# main.net
KiCad netlist of a schematic drawn in Altium Designer
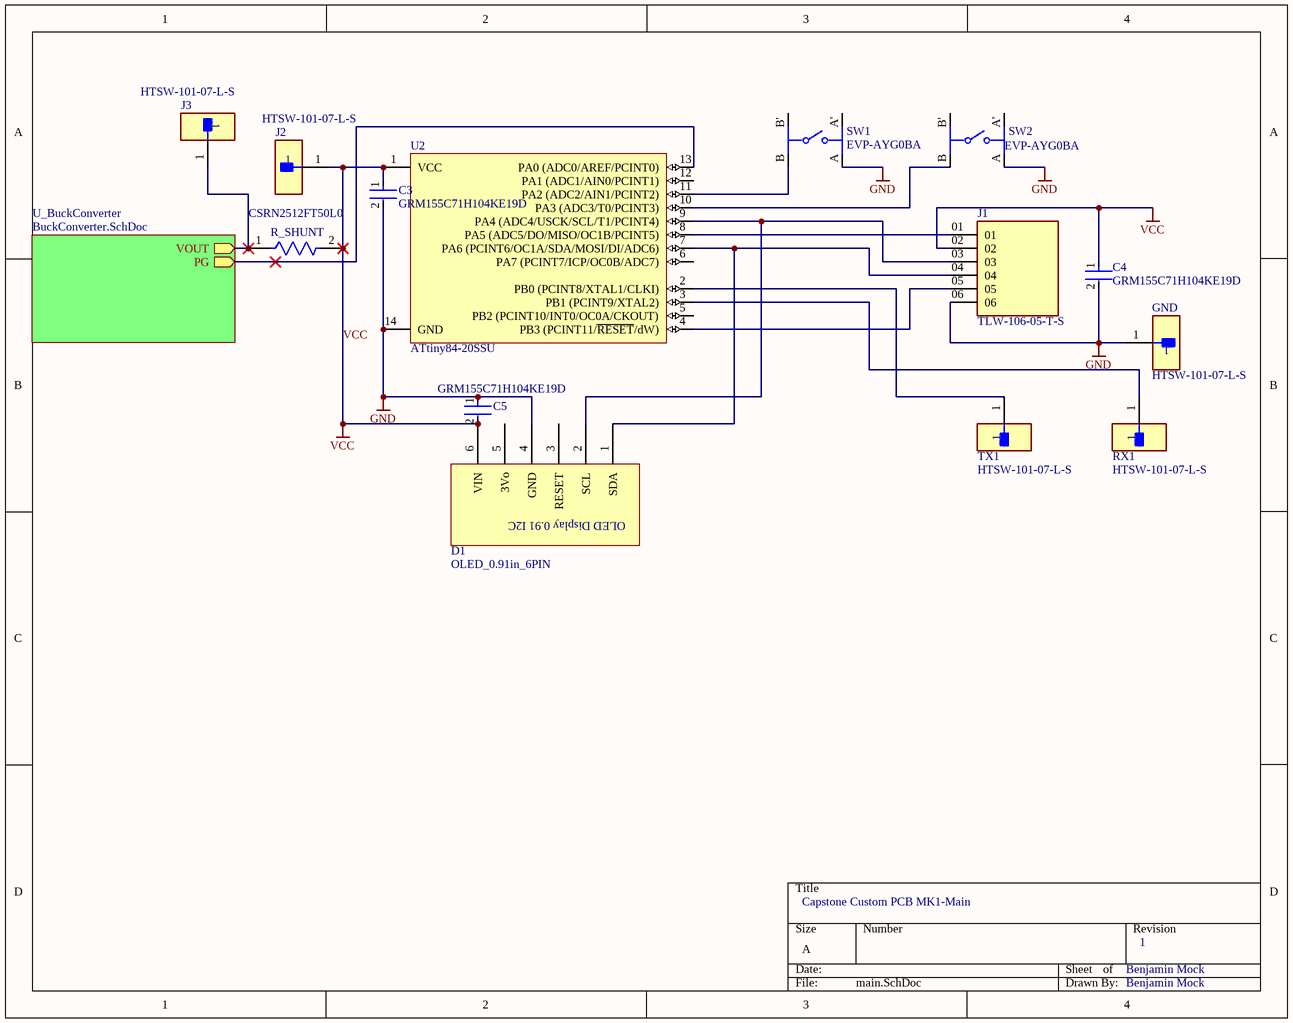
[diagram p0: main.SchDoc]

(export (version "E")
  (design (tool "Eeschema 10.0.6"))
  (components
    (comp (ref "C3")
      (value "GRM155C71H104KE19D")
      (footprint "FP-GRM155-0_05-MFG")
      (description "Chip Multilayer Ceramic Capacitors for General Purpose, 0402, 0.10uF, X7S, 22%, 10%, 50V")
      (fields (field (name "TOLERANCE") "10%"))
      (libsource (lib "Altium Content Vault") (part "02cd4be3c70576c341d710602a673aa"))
    )
    (comp (ref "C4")
      (value "GRM155C71H104KE19D")
      (footprint "FP-GRM155-0_05-MFG")
      (description "Chip Multilayer Ceramic Capacitors for General Purpose, 0402, 0.10uF, X7S, 22%, 10%, 50V")
      (fields (field (name "TOLERANCE") "10%"))
      (libsource (lib "Altium Content Vault") (part "02cd4be3c70576c341d710602a673aa"))
    )
    (comp (ref "C5")
      (value "GRM155C71H104KE19D")
      (footprint "FP-GRM155-0_05-MFG")
      (description "Chip Multilayer Ceramic Capacitors for General Purpose, 0402, 0.10uF, X7S, 22%, 10%, 50V")
      (fields (field (name "TOLERANCE") "10%"))
      (libsource (lib "Altium Content Vault") (part "02cd4be3c70576c341d710602a673aa"))
    )
    (comp (ref "D1")
      (value "OLED_0.91in_6PIN")
      (footprint "PCBComponent_1")
      (libsource (lib "OLED_Display") (part "OLED_0.91in_6PIN"))
    )
    (comp (ref "GND")
      (value "HTSW-101-07-L-S")
      (footprint "FP-HTSW-101-07-L-S-MFG")
      (description "CONN HEADER VERT 1POS")
      (libsource (lib "Altium Content Vault") (part "dd45045ce8184df9e99e12baf3f412c"))
    )
    (comp (ref "J1")
      (value "TLW-106-05-T-S")
      (footprint "SAMTEC_TLW-106-05-T-S")
      (libsource (lib "TLW-106-05-T-S") (part "TLW-106-05-T-S"))
    )
    (comp (ref "J2")
      (value "HTSW-101-07-L-S")
      (footprint "FP-HTSW-101-07-L-S-MFG")
      (description "CONN HEADER VERT 1POS")
      (libsource (lib "") (part "dd45045ce8184df9e99e12baf3f412c_2"))
    )
    (comp (ref "J3")
      (value "HTSW-101-07-L-S")
      (footprint "FP-HTSW-101-07-L-S-MFG")
      (description "CONN HEADER VERT 1POS")
      (libsource (lib "") (part "dd45045ce8184df9e99e12baf3f412c_3"))
    )
    (comp (ref "RX1")
      (value "HTSW-101-07-L-S")
      (footprint "FP-HTSW-101-07-L-S-MFG")
      (description "CONN HEADER VERT 1POS")
      (libsource (lib "") (part "dd45045ce8184df9e99e12baf3f412c_1"))
    )
    (comp (ref "R_SHUNT")
      (value "CSRN2512FT50L0")
      (footprint "FP-CSRN2512-IPC_B")
      (description "Res Thick Film 2512 50mΩ 1% 2W ±200ppm/°C Molded SMD Plastic T/R")
      (fields (field (name "TOLERANCE") "1%"))
      (libsource (lib "Altium Content Vault") (part "1029c3af85768c4190bb7ad29bc67b5"))
    )
    (comp (ref "SW1")
      (value "EVP-AYG0BA")
      (footprint "FP-EVP-AYG0BA-MFG")
      (description "SWITCH TACTILE SPST-NO 0.02A 15V")
      (libsource (lib "Altium Content Vault") (part "ac634b74112f77252d8361be3a8fb16"))
    )
    (comp (ref "SW2")
      (value "EVP-AYG0BA")
      (footprint "FP-EVP-AYG0BA-MFG")
      (description "SWITCH TACTILE SPST-NO 0.02A 15V")
      (libsource (lib "Altium Content Vault") (part "ac634b74112f77252d8361be3a8fb16"))
    )
    (comp (ref "TX1")
      (value "HTSW-101-07-L-S")
      (footprint "FP-HTSW-101-07-L-S-MFG")
      (description "CONN HEADER VERT 1POS")
      (libsource (lib "") (part "dd45045ce8184df9e99e12baf3f412c_1"))
    )
    (comp (ref "U2")
      (value "ATtiny84-20SSU")
      (footprint "14S1_N")
      (libsource (lib "Altium Content Vault") (part "MC-8B-ATTINY24V-IL14"))
    )
  )
  (nets
    (net (code "1") (name "/PG") (class "Default")
      (node (ref "U2") (pin "13") (pinfunction "PA0_(ADC0/AREF/PCINT0)_13") (pintype "bidirectional"))
    )
    (net (code "2") (name "/VOUT") (class "Default")
      (node (ref "J3") (pin "1") (pinfunction "1_1") (pintype "passive"))
      (node (ref "R_SHUNT") (pin "1") (pinfunction "1_1") (pintype "passive"))
    )
    (net (code "3") (name "GND") (class "Default")
      (node (ref "C3") (pin "2") (pinfunction "2_2") (pintype "passive"))
      (node (ref "C4") (pin "2") (pinfunction "2_2") (pintype "passive"))
      (node (ref "C5") (pin "1") (pinfunction "1_1") (pintype "passive"))
      (node (ref "D1") (pin "4") (pinfunction "GND_4") (pintype "passive"))
      (node (ref "GND") (pin "1") (pinfunction "1_1") (pintype "passive"))
      (node (ref "J1") (pin "06") (pinfunction "06_06") (pintype "passive"))
      (node (ref "SW1") (pin "A") (pinfunction "A_A") (pintype "passive"))
      (node (ref "SW2") (pin "A") (pinfunction "A_A") (pintype "passive"))
      (node (ref "U2") (pin "14") (pinfunction "GND_14") (pintype "power_in"))
    )
    (net (code "4") (name "Net-(D1-SCL)") (class "Default")
      (node (ref "D1") (pin "2") (pinfunction "SCL_2") (pintype "passive"))
      (node (ref "J1") (pin "03") (pinfunction "03_03") (pintype "passive"))
      (node (ref "U2") (pin "9") (pinfunction "PA4_(ADC4/USCK/SCL/T1/PCINT4)_9") (pintype "bidirectional"))
    )
    (net (code "5") (name "Net-(D1-SDA)") (class "Default")
      (node (ref "D1") (pin "1") (pinfunction "SDA_1") (pintype "passive"))
      (node (ref "J1") (pin "04") (pinfunction "04_04") (pintype "passive"))
      (node (ref "U2") (pin "7") (pinfunction "PA6_(PCINT6/OC1A/SDA/MOSI/DI/ADC6)_7") (pintype "bidirectional"))
    )
    (net (code "6") (name "Net-(U2-PA2_(ADC2{slash}AIN1{slash}PCINT2))") (class "Default")
      (node (ref "SW1") (pin "B") (pinfunction "B_B") (pintype "passive"))
      (node (ref "U2") (pin "11") (pinfunction "PA2_(ADC2/AIN1/PCINT2)_11") (pintype "bidirectional"))
    )
    (net (code "7") (name "Net-(U2-PA3_(ADC3{slash}T0{slash}PCINT3))") (class "Default")
      (node (ref "SW2") (pin "B") (pinfunction "B_B") (pintype "passive"))
      (node (ref "U2") (pin "10") (pinfunction "PA3_(ADC3/T0/PCINT3)_10") (pintype "bidirectional"))
    )
    (net (code "8") (name "Net-(U2-PA5_(ADC5{slash}DO{slash}MISO{slash}OC1B{slash}PCINT5))") (class "Default")
      (node (ref "J1") (pin "01") (pinfunction "01_01") (pintype "passive"))
      (node (ref "U2") (pin "8") (pinfunction "PA5_(ADC5/DO/MISO/OC1B/PCINT5)_8") (pintype "bidirectional"))
    )
    (net (code "9") (name "Net-(U2-PB0_(PCINT8{slash}XTAL1{slash}CLKI))") (class "Default")
      (node (ref "TX1") (pin "1") (pinfunction "1_1") (pintype "passive"))
      (node (ref "U2") (pin "2") (pinfunction "PB0_(PCINT8/XTAL1/CLKI)_2") (pintype "bidirectional"))
    )
    (net (code "10") (name "Net-(U2-PB1_(PCINT9{slash}XTAL2))") (class "Default")
      (node (ref "RX1") (pin "1") (pinfunction "1_1") (pintype "passive"))
      (node (ref "U2") (pin "3") (pinfunction "PB1_(PCINT9/XTAL2)_3") (pintype "bidirectional"))
    )
    (net (code "11") (name "Net-(U2-PB3_(PCINT11{slash}~{RESET}{slash}dW))") (class "Default")
      (node (ref "J1") (pin "05") (pinfunction "05_05") (pintype "passive"))
      (node (ref "U2") (pin "4") (pinfunction "PB3_(PCINT11/~{RESET}/dW)_4") (pintype "bidirectional"))
    )
    (net (code "12") (name "VCC") (class "Default")
      (node (ref "C3") (pin "1") (pinfunction "1_1") (pintype "passive"))
      (node (ref "C4") (pin "1") (pinfunction "1_1") (pintype "passive"))
      (node (ref "C5") (pin "2") (pinfunction "2_2") (pintype "passive"))
      (node (ref "D1") (pin "6") (pinfunction "VIN_6") (pintype "passive"))
      (node (ref "J1") (pin "02") (pinfunction "02_02") (pintype "passive"))
      (node (ref "J2") (pin "1") (pinfunction "1_1") (pintype "passive"))
      (node (ref "R_SHUNT") (pin "2") (pinfunction "2_2") (pintype "passive"))
      (node (ref "U2") (pin "1") (pinfunction "VCC_1") (pintype "power_in"))
    )
    (net (code "13") (name "unconnected-(D1-3Vo-Pad5)") (class "Default")
      (node (ref "D1") (pin "5") (pinfunction "3Vo_5") (pintype "passive"))
    )
    (net (code "14") (name "unconnected-(D1-RESET-Pad3)") (class "Default")
      (node (ref "D1") (pin "3") (pinfunction "RESET_3") (pintype "passive"))
    )
    (net (code "15") (name "unconnected-(SW1-PadA')") (class "Default")
      (node (ref "SW1") (pin "A'") (pinfunction "A'_A'") (pintype "passive"))
    )
    (net (code "16") (name "unconnected-(SW1-PadB')") (class "Default")
      (node (ref "SW1") (pin "B'") (pinfunction "B'_B'") (pintype "passive"))
    )
    (net (code "17") (name "unconnected-(SW2-PadA')") (class "Default")
      (node (ref "SW2") (pin "A'") (pinfunction "A'_A'") (pintype "passive"))
    )
    (net (code "18") (name "unconnected-(SW2-PadB')") (class "Default")
      (node (ref "SW2") (pin "B'") (pinfunction "B'_B'") (pintype "passive"))
    )
    (net (code "19") (name "unconnected-(U2-PA1_(ADC1{slash}AIN0{slash}PCINT1)-Pad12)") (class "Default")
      (node (ref "U2") (pin "12") (pinfunction "PA1_(ADC1/AIN0/PCINT1)_12") (pintype "bidirectional"))
    )
    (net (code "20") (name "unconnected-(U2-PA7_(PCINT7{slash}ICP{slash}OC0B{slash}ADC7)-Pad6)") (class "Default")
      (node (ref "U2") (pin "6") (pinfunction "PA7_(PCINT7/ICP/OC0B/ADC7)_6") (pintype "bidirectional"))
    )
    (net (code "21") (name "unconnected-(U2-PB2_(PCINT10{slash}INT0{slash}OC0A{slash}CKOUT)-Pad5)") (class "Default")
      (node (ref "U2") (pin "5") (pinfunction "PB2_(PCINT10/INT0/OC0A/CKOUT)_5") (pintype "bidirectional"))
    )
  )
)
